# Antenna_Schematic.net
KiCad netlist of a schematic drawn in EAGLE
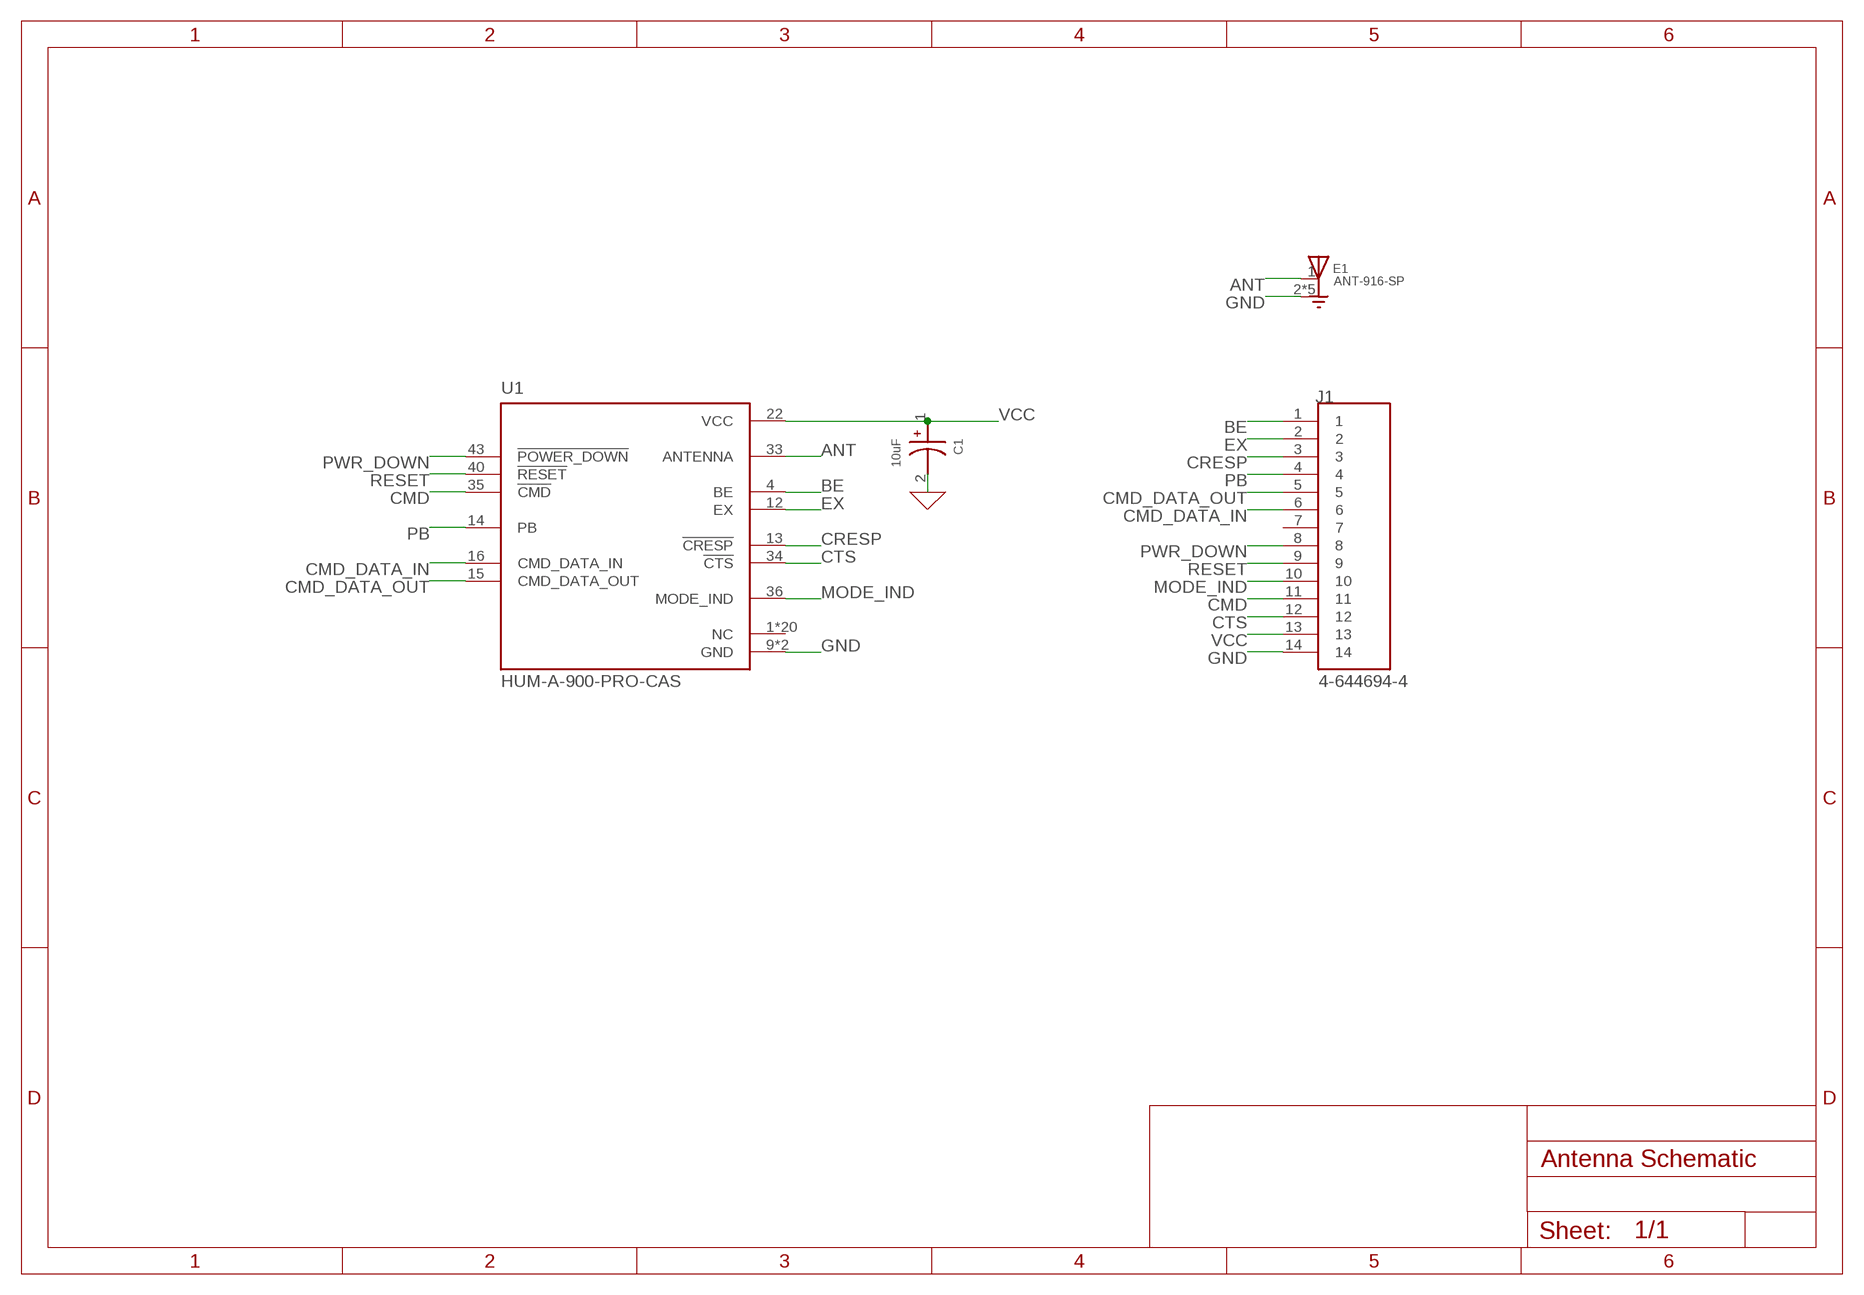
[diagram p0: schematic, sheet 1]

(export (version "E")
  (design (tool "Eeschema 10.0.6"))
  (components
    (comp (ref "C1")
      (value "10uF")
      (footprint "eagle-import:CAPMP3216X180N")
      (fields (field (name "MF") "AVX Interconnect / Elco") (field (name "MP") "TAJA106K010RNJ"))
      (libsource (lib "eagle-import") (part "TAJA106K010RNJ"))
    )
    (comp (ref "E1")
      (value "ANT-916-SP")
      (footprint "eagle-import:XDCR_ANT-916-SP")
      (fields (field (name "MF") "Linx Technologies"))
      (libsource (lib "eagle-import") (part "ANT-916-SP"))
    )
    (comp (ref "J1")
      (value "4-644694-4")
      (footprint "eagle-import:TE_4-644694-4")
      (fields (field (name "MF") "TE Connectivity"))
      (libsource (lib "eagle-import") (part "4-644694-4"))
    )
    (comp (ref "U1")
      (value "HUM-A-900-PRO-CAS")
      (footprint "eagle-import:XCVR_HUM-A-900-PRO-CAS")
      (fields (field (name "MF") "Linx"))
      (libsource (lib "eagle-import") (part "HUM-A-900-PRO-CAS"))
    )
  )
  (nets
    (net (code "1") (name "/ANT") (class "Default")
      (node (ref "E1") (pin "1") (pinfunction "FEEDING_1") (pintype "passive"))
      (node (ref "U1") (pin "33") (pinfunction "ANTENNA_33") (pintype "bidirectional"))
    )
    (net (code "2") (name "/BE") (class "Default")
      (node (ref "J1") (pin "1") (pinfunction "1_1") (pintype "passive"))
      (node (ref "U1") (pin "4") (pinfunction "BE_4") (pintype "output"))
    )
    (net (code "3") (name "/CMD") (class "Default")
      (node (ref "J1") (pin "11") (pinfunction "11_11") (pintype "passive"))
      (node (ref "U1") (pin "35") (pinfunction "~{CMD}_35") (pintype "input"))
    )
    (net (code "4") (name "/CMD_DATA_IN") (class "Default")
      (node (ref "J1") (pin "6") (pinfunction "6_6") (pintype "passive"))
      (node (ref "U1") (pin "16") (pinfunction "CMD_DATA_IN_16") (pintype "input"))
    )
    (net (code "5") (name "/CMD_DATA_OUT") (class "Default")
      (node (ref "J1") (pin "5") (pinfunction "5_5") (pintype "passive"))
      (node (ref "U1") (pin "15") (pinfunction "CMD_DATA_OUT_15") (pintype "output"))
    )
    (net (code "6") (name "/CRESP") (class "Default")
      (node (ref "J1") (pin "3") (pinfunction "3_3") (pintype "passive"))
      (node (ref "U1") (pin "13") (pinfunction "~{CRESP}_13") (pintype "output"))
    )
    (net (code "7") (name "/CTS") (class "Default")
      (node (ref "J1") (pin "12") (pinfunction "12_12") (pintype "passive"))
      (node (ref "U1") (pin "34") (pinfunction "~{CTS}_34") (pintype "output"))
    )
    (net (code "8") (name "/EX") (class "Default")
      (node (ref "J1") (pin "2") (pinfunction "2_2") (pintype "passive"))
      (node (ref "U1") (pin "12") (pinfunction "EX_12") (pintype "output"))
    )
    (net (code "9") (name "/MODE_IND") (class "Default")
      (node (ref "J1") (pin "10") (pinfunction "10_10") (pintype "passive"))
      (node (ref "U1") (pin "36") (pinfunction "MODE_IND_36") (pintype "output"))
    )
    (net (code "10") (name "/PB") (class "Default")
      (node (ref "J1") (pin "4") (pinfunction "4_4") (pintype "passive"))
      (node (ref "U1") (pin "14") (pinfunction "PB_14") (pintype "input"))
    )
    (net (code "11") (name "/PWR_DOWN") (class "Default")
      (node (ref "J1") (pin "8") (pinfunction "8_8") (pintype "passive"))
      (node (ref "U1") (pin "43") (pinfunction "~{POWER_DOWN}_43") (pintype "input"))
    )
    (net (code "12") (name "/RESET") (class "Default")
      (node (ref "J1") (pin "9") (pinfunction "9_9") (pintype "passive"))
      (node (ref "U1") (pin "40") (pinfunction "~{RESET}_40") (pintype "input"))
    )
    (net (code "13") (name "/VCC") (class "Default")
      (node (ref "C1") (pin "1") (pinfunction "1_1") (pintype "passive"))
      (node (ref "J1") (pin "13") (pinfunction "13_13") (pintype "passive"))
      (node (ref "U1") (pin "22") (pinfunction "VCC_22") (pintype "power_in"))
    )
    (net (code "14") (name "GND") (class "Default")
      (node (ref "C1") (pin "2") (pinfunction "2_2") (pintype "passive"))
      (node (ref "E1") (pin "2") (pinfunction "GND_2") (pintype "power_in"))
      (node (ref "E1") (pin "3") (pinfunction "GND_3") (pintype "power_in"))
      (node (ref "E1") (pin "4") (pinfunction "GND_4") (pintype "power_in"))
      (node (ref "E1") (pin "5") (pinfunction "GND_5") (pintype "power_in"))
      (node (ref "E1") (pin "6") (pinfunction "GND_6") (pintype "power_in"))
      (node (ref "J1") (pin "14") (pinfunction "14_14") (pintype "passive"))
      (node (ref "U1") (pin "32") (pinfunction "GND_32") (pintype "power_in"))
      (node (ref "U1") (pin "9") (pinfunction "GND_9") (pintype "power_in"))
    )
    (net (code "15") (name "unconnected-(J1-Pad7)") (class "Default")
      (node (ref "J1") (pin "7") (pinfunction "7_7") (pintype "passive"))
    )
    (net (code "16") (name "unconnected-(U1-NC-Pad1)") (class "Default")
      (node (ref "U1") (pin "1") (pinfunction "NC_1") (pintype "no_connect"))
    )
    (net (code "17") (name "unconnected-(U1-NC-Pad2)") (class "Default")
      (node (ref "U1") (pin "2") (pinfunction "NC_2") (pintype "no_connect"))
    )
    (net (code "18") (name "unconnected-(U1-NC-Pad3)") (class "Default")
      (node (ref "U1") (pin "3") (pinfunction "NC_3") (pintype "no_connect"))
    )
    (net (code "19") (name "unconnected-(U1-NC-Pad5)") (class "Default")
      (node (ref "U1") (pin "5") (pinfunction "NC_5") (pintype "no_connect"))
    )
    (net (code "20") (name "unconnected-(U1-NC-Pad6)") (class "Default")
      (node (ref "U1") (pin "6") (pinfunction "NC_6") (pintype "no_connect"))
    )
    (net (code "21") (name "unconnected-(U1-NC-Pad7)") (class "Default")
      (node (ref "U1") (pin "7") (pinfunction "NC_7") (pintype "no_connect"))
    )
    (net (code "22") (name "unconnected-(U1-NC-Pad8)") (class "Default")
      (node (ref "U1") (pin "8") (pinfunction "NC_8") (pintype "no_connect"))
    )
    (net (code "23") (name "unconnected-(U1-NC-Pad10)") (class "Default")
      (node (ref "U1") (pin "10") (pinfunction "NC_10") (pintype "no_connect"))
    )
    (net (code "24") (name "unconnected-(U1-NC-Pad11)") (class "Default")
      (node (ref "U1") (pin "11") (pinfunction "NC_11") (pintype "no_connect"))
    )
    (net (code "25") (name "unconnected-(U1-NC-Pad17)") (class "Default")
      (node (ref "U1") (pin "17") (pinfunction "NC_17") (pintype "no_connect"))
    )
    (net (code "26") (name "unconnected-(U1-NC-Pad18)") (class "Default")
      (node (ref "U1") (pin "18") (pinfunction "NC_18") (pintype "no_connect"))
    )
    (net (code "27") (name "unconnected-(U1-NC-Pad19)") (class "Default")
      (node (ref "U1") (pin "19") (pinfunction "NC_19") (pintype "no_connect"))
    )
    (net (code "28") (name "unconnected-(U1-NC-Pad20)") (class "Default")
      (node (ref "U1") (pin "20") (pinfunction "NC_20") (pintype "no_connect"))
    )
    (net (code "29") (name "unconnected-(U1-NC-Pad21)") (class "Default")
      (node (ref "U1") (pin "21") (pinfunction "NC_21") (pintype "no_connect"))
    )
    (net (code "30") (name "unconnected-(U1-NC-Pad37)") (class "Default")
      (node (ref "U1") (pin "37") (pinfunction "NC_37") (pintype "no_connect"))
    )
    (net (code "31") (name "unconnected-(U1-NC-Pad38)") (class "Default")
      (node (ref "U1") (pin "38") (pinfunction "NC_38") (pintype "no_connect"))
    )
    (net (code "32") (name "unconnected-(U1-NC-Pad39)") (class "Default")
      (node (ref "U1") (pin "39") (pinfunction "NC_39") (pintype "no_connect"))
    )
    (net (code "33") (name "unconnected-(U1-NC-Pad41)") (class "Default")
      (node (ref "U1") (pin "41") (pinfunction "NC_41") (pintype "no_connect"))
    )
    (net (code "34") (name "unconnected-(U1-NC-Pad42)") (class "Default")
      (node (ref "U1") (pin "42") (pinfunction "NC_42") (pintype "no_connect"))
    )
    (net (code "35") (name "unconnected-(U1-NC-Pad44)") (class "Default")
      (node (ref "U1") (pin "44") (pinfunction "NC_44") (pintype "no_connect"))
    )
  )
)
